# Pin_Headers.net
KiCad netlist of a schematic drawn in Altium Designer
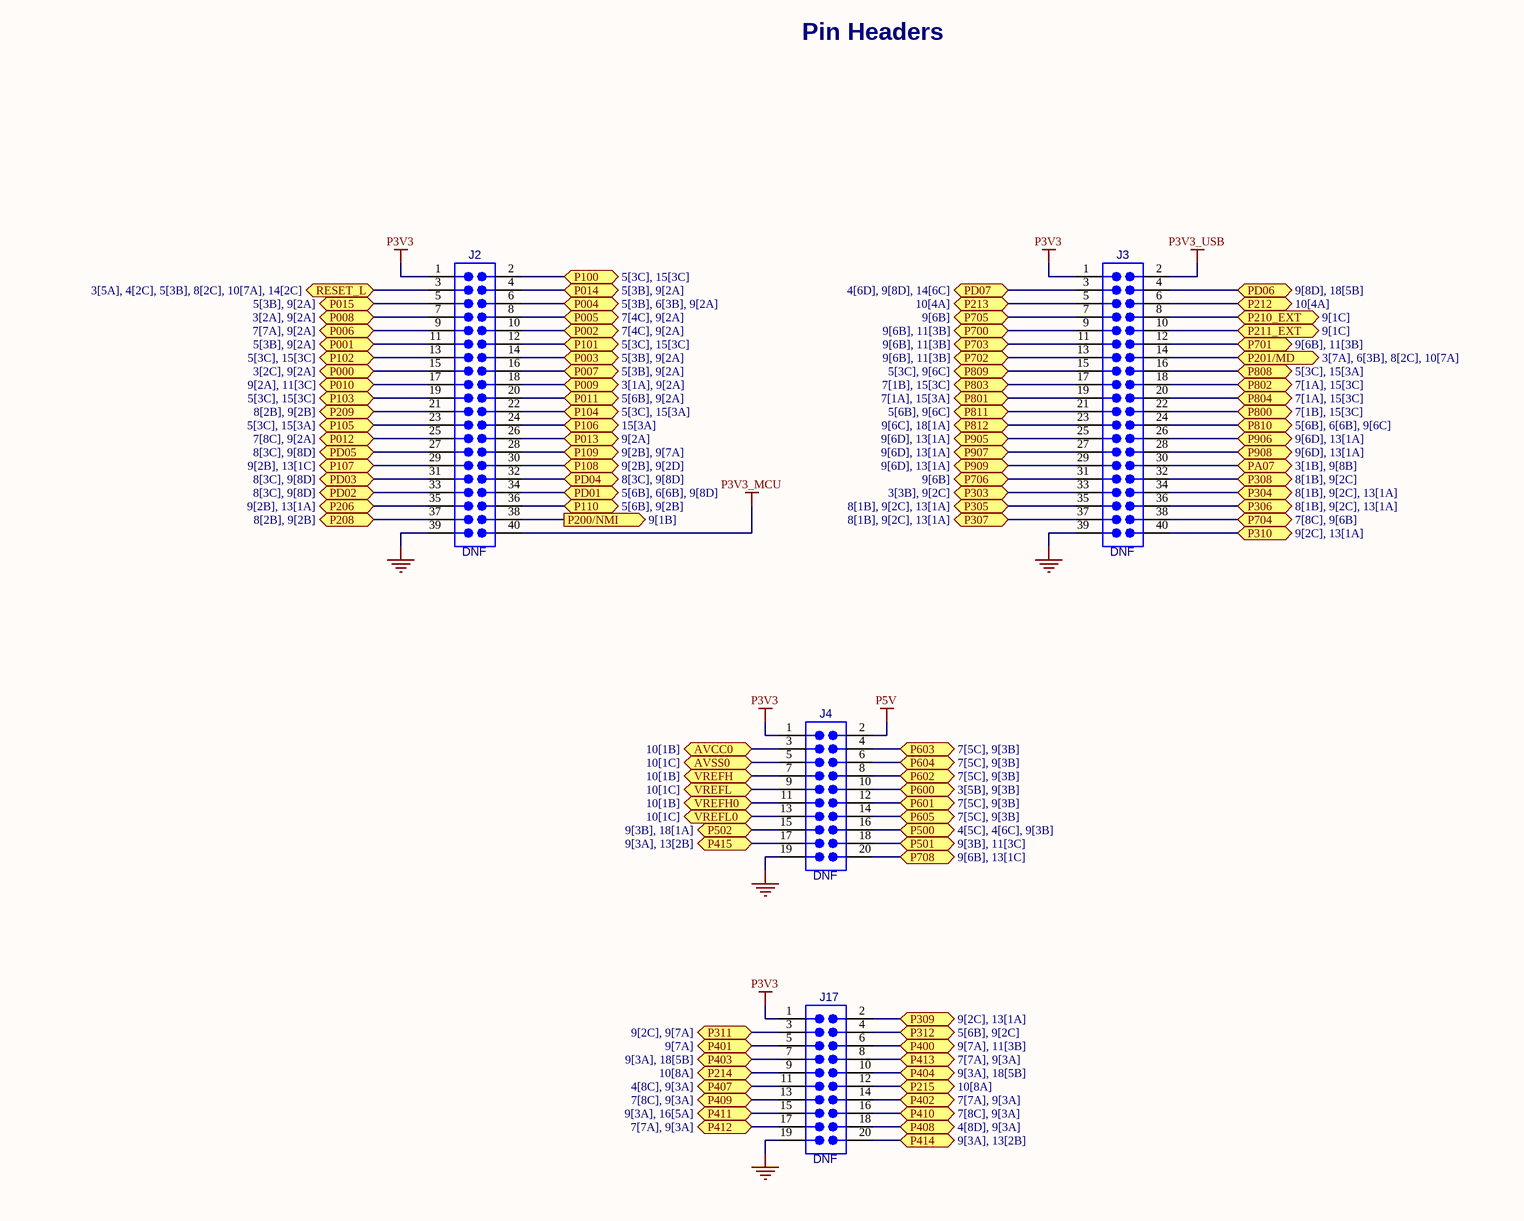
[diagram p0: Pin Headers.SchDoc]

(export (version "E")
  (design (tool "Eeschema 10.0.6"))
  (components
    (comp (ref "J2")
      (value "CON_040")
      (footprint "wue_61304021121")
      (description "Header,40way,2row,vertical,2.54mm,THT")
      (fields (field (name "DNF") "DNF"))
      (libsource (lib "ek-ra8d2_mp - Customer") (part "CON_040"))
    )
    (comp (ref "J3")
      (value "CON_040")
      (footprint "wue_61304021121")
      (description "Header,40way,2row,vertical,2.54mm,THT")
      (fields (field (name "DNF") "DNF"))
      (libsource (lib "ek-ra8d2_mp - Customer") (part "CON_040"))
    )
    (comp (ref "J4")
      (value "CON_020")
      (footprint "wue_61302021121")
      (description "Header,20way,2row,vertical,2.54mm,THT")
      (fields (field (name "DNF") "DNF"))
      (libsource (lib "ek-ra8d2_mp - Customer") (part "CON_020"))
    )
    (comp (ref "J17")
      (value "CON_020")
      (footprint "wue_61302021121")
      (description "Header,20way,2row,vertical,2.54mm,THT")
      (fields (field (name "DNF") "DNF"))
      (libsource (lib "ek-ra8d2_mp - Customer") (part "CON_020"))
    )
  )
  (nets
    (net (code "1") (name "/AVCC0") (class "Default")
      (node (ref "J4") (pin "3") (pinfunction "3_3") (pintype "passive"))
    )
    (net (code "2") (name "/AVSS0") (class "Default")
      (node (ref "J4") (pin "5") (pinfunction "5_5") (pintype "passive"))
    )
    (net (code "3") (name "/P000") (class "Default")
      (node (ref "J2") (pin "15") (pinfunction "15_15") (pintype "passive"))
    )
    (net (code "4") (name "/P001") (class "Default")
      (node (ref "J2") (pin "11") (pinfunction "11_11") (pintype "passive"))
    )
    (net (code "5") (name "/P002") (class "Default")
      (node (ref "J2") (pin "10") (pinfunction "10_10") (pintype "passive"))
    )
    (net (code "6") (name "/P003") (class "Default")
      (node (ref "J2") (pin "14") (pinfunction "14_14") (pintype "passive"))
    )
    (net (code "7") (name "/P004") (class "Default")
      (node (ref "J2") (pin "6") (pinfunction "6_6") (pintype "passive"))
    )
    (net (code "8") (name "/P005") (class "Default")
      (node (ref "J2") (pin "8") (pinfunction "8_8") (pintype "passive"))
    )
    (net (code "9") (name "/P006") (class "Default")
      (node (ref "J2") (pin "9") (pinfunction "9_9") (pintype "passive"))
    )
    (net (code "10") (name "/P007") (class "Default")
      (node (ref "J2") (pin "16") (pinfunction "16_16") (pintype "passive"))
    )
    (net (code "11") (name "/P008") (class "Default")
      (node (ref "J2") (pin "7") (pinfunction "7_7") (pintype "passive"))
    )
    (net (code "12") (name "/P009") (class "Default")
      (node (ref "J2") (pin "18") (pinfunction "18_18") (pintype "passive"))
    )
    (net (code "13") (name "/P010") (class "Default")
      (node (ref "J2") (pin "17") (pinfunction "17_17") (pintype "passive"))
    )
    (net (code "14") (name "/P011") (class "Default")
      (node (ref "J2") (pin "20") (pinfunction "20_20") (pintype "passive"))
    )
    (net (code "15") (name "/P012") (class "Default")
      (node (ref "J2") (pin "25") (pinfunction "25_25") (pintype "passive"))
    )
    (net (code "16") (name "/P013") (class "Default")
      (node (ref "J2") (pin "26") (pinfunction "26_26") (pintype "passive"))
    )
    (net (code "17") (name "/P014") (class "Default")
      (node (ref "J2") (pin "4") (pinfunction "4_4") (pintype "passive"))
    )
    (net (code "18") (name "/P015") (class "Default")
      (node (ref "J2") (pin "5") (pinfunction "5_5") (pintype "passive"))
    )
    (net (code "19") (name "/P100") (class "Default")
      (node (ref "J2") (pin "2") (pinfunction "2_2") (pintype "passive"))
    )
    (net (code "20") (name "/P101") (class "Default")
      (node (ref "J2") (pin "12") (pinfunction "12_12") (pintype "passive"))
    )
    (net (code "21") (name "/P102") (class "Default")
      (node (ref "J2") (pin "13") (pinfunction "13_13") (pintype "passive"))
    )
    (net (code "22") (name "/P103") (class "Default")
      (node (ref "J2") (pin "19") (pinfunction "19_19") (pintype "passive"))
    )
    (net (code "23") (name "/P104") (class "Default")
      (node (ref "J2") (pin "22") (pinfunction "22_22") (pintype "passive"))
    )
    (net (code "24") (name "/P105") (class "Default")
      (node (ref "J2") (pin "23") (pinfunction "23_23") (pintype "passive"))
    )
    (net (code "25") (name "/P106") (class "Default")
      (node (ref "J2") (pin "24") (pinfunction "24_24") (pintype "passive"))
    )
    (net (code "26") (name "/P107") (class "Default")
      (node (ref "J2") (pin "29") (pinfunction "29_29") (pintype "passive"))
    )
    (net (code "27") (name "/P108") (class "Default")
      (node (ref "J2") (pin "30") (pinfunction "30_30") (pintype "passive"))
    )
    (net (code "28") (name "/P109") (class "Default")
      (node (ref "J2") (pin "28") (pinfunction "28_28") (pintype "passive"))
    )
    (net (code "29") (name "/P110") (class "Default")
      (node (ref "J2") (pin "36") (pinfunction "36_36") (pintype "passive"))
    )
    (net (code "30") (name "/P200{slash}NMI") (class "Default")
      (node (ref "J2") (pin "38") (pinfunction "38_38") (pintype "passive"))
    )
    (net (code "31") (name "/P201{slash}MD") (class "Default")
      (node (ref "J3") (pin "14") (pinfunction "14_14") (pintype "passive"))
    )
    (net (code "32") (name "/P206") (class "Default")
      (node (ref "J2") (pin "35") (pinfunction "35_35") (pintype "passive"))
    )
    (net (code "33") (name "/P208") (class "Default")
      (node (ref "J2") (pin "37") (pinfunction "37_37") (pintype "passive"))
    )
    (net (code "34") (name "/P209") (class "Default")
      (node (ref "J2") (pin "21") (pinfunction "21_21") (pintype "passive"))
    )
    (net (code "35") (name "/P210_EXT") (class "Default")
      (node (ref "J3") (pin "8") (pinfunction "8_8") (pintype "passive"))
    )
    (net (code "36") (name "/P211_EXT") (class "Default")
      (node (ref "J3") (pin "10") (pinfunction "10_10") (pintype "passive"))
    )
    (net (code "37") (name "/P212") (class "Default")
      (node (ref "J3") (pin "6") (pinfunction "6_6") (pintype "passive"))
    )
    (net (code "38") (name "/P213") (class "Default")
      (node (ref "J3") (pin "5") (pinfunction "5_5") (pintype "passive"))
    )
    (net (code "39") (name "/P214") (class "Default")
      (node (ref "J17") (pin "9") (pinfunction "9_9") (pintype "passive"))
    )
    (net (code "40") (name "/P215") (class "Default")
      (node (ref "J17") (pin "12") (pinfunction "12_12") (pintype "passive"))
    )
    (net (code "41") (name "/P303") (class "Default")
      (node (ref "J3") (pin "33") (pinfunction "33_33") (pintype "passive"))
    )
    (net (code "42") (name "/P304") (class "Default")
      (node (ref "J3") (pin "34") (pinfunction "34_34") (pintype "passive"))
    )
    (net (code "43") (name "/P305") (class "Default")
      (node (ref "J3") (pin "35") (pinfunction "35_35") (pintype "passive"))
    )
    (net (code "44") (name "/P306") (class "Default")
      (node (ref "J3") (pin "36") (pinfunction "36_36") (pintype "passive"))
    )
    (net (code "45") (name "/P307") (class "Default")
      (node (ref "J3") (pin "37") (pinfunction "37_37") (pintype "passive"))
    )
    (net (code "46") (name "/P308") (class "Default")
      (node (ref "J3") (pin "32") (pinfunction "32_32") (pintype "passive"))
    )
    (net (code "47") (name "/P309") (class "Default")
      (node (ref "J17") (pin "2") (pinfunction "2_2") (pintype "passive"))
    )
    (net (code "48") (name "/P310") (class "Default")
      (node (ref "J3") (pin "40") (pinfunction "40_40") (pintype "passive"))
    )
    (net (code "49") (name "/P311") (class "Default")
      (node (ref "J17") (pin "3") (pinfunction "3_3") (pintype "passive"))
    )
    (net (code "50") (name "/P312") (class "Default")
      (node (ref "J17") (pin "4") (pinfunction "4_4") (pintype "passive"))
    )
    (net (code "51") (name "/P400") (class "Default")
      (node (ref "J17") (pin "6") (pinfunction "6_6") (pintype "passive"))
    )
    (net (code "52") (name "/P401") (class "Default")
      (node (ref "J17") (pin "5") (pinfunction "5_5") (pintype "passive"))
    )
    (net (code "53") (name "/P402") (class "Default")
      (node (ref "J17") (pin "14") (pinfunction "14_14") (pintype "passive"))
    )
    (net (code "54") (name "/P403") (class "Default")
      (node (ref "J17") (pin "7") (pinfunction "7_7") (pintype "passive"))
    )
    (net (code "55") (name "/P404") (class "Default")
      (node (ref "J17") (pin "10") (pinfunction "10_10") (pintype "passive"))
    )
    (net (code "56") (name "/P407") (class "Default")
      (node (ref "J17") (pin "11") (pinfunction "11_11") (pintype "passive"))
    )
    (net (code "57") (name "/P408") (class "Default")
      (node (ref "J17") (pin "18") (pinfunction "18_18") (pintype "passive"))
    )
    (net (code "58") (name "/P409") (class "Default")
      (node (ref "J17") (pin "13") (pinfunction "13_13") (pintype "passive"))
    )
    (net (code "59") (name "/P410") (class "Default")
      (node (ref "J17") (pin "16") (pinfunction "16_16") (pintype "passive"))
    )
    (net (code "60") (name "/P411") (class "Default")
      (node (ref "J17") (pin "15") (pinfunction "15_15") (pintype "passive"))
    )
    (net (code "61") (name "/P412") (class "Default")
      (node (ref "J17") (pin "17") (pinfunction "17_17") (pintype "passive"))
    )
    (net (code "62") (name "/P413") (class "Default")
      (node (ref "J17") (pin "8") (pinfunction "8_8") (pintype "passive"))
    )
    (net (code "63") (name "/P414") (class "Default")
      (node (ref "J17") (pin "20") (pinfunction "20_20") (pintype "passive"))
    )
    (net (code "64") (name "/P415") (class "Default")
      (node (ref "J4") (pin "17") (pinfunction "17_17") (pintype "passive"))
    )
    (net (code "65") (name "/P500") (class "Default")
      (node (ref "J4") (pin "16") (pinfunction "16_16") (pintype "passive"))
    )
    (net (code "66") (name "/P501") (class "Default")
      (node (ref "J4") (pin "18") (pinfunction "18_18") (pintype "passive"))
    )
    (net (code "67") (name "/P502") (class "Default")
      (node (ref "J4") (pin "15") (pinfunction "15_15") (pintype "passive"))
    )
    (net (code "68") (name "/P600") (class "Default")
      (node (ref "J4") (pin "10") (pinfunction "10_10") (pintype "passive"))
    )
    (net (code "69") (name "/P601") (class "Default")
      (node (ref "J4") (pin "12") (pinfunction "12_12") (pintype "passive"))
    )
    (net (code "70") (name "/P602") (class "Default")
      (node (ref "J4") (pin "8") (pinfunction "8_8") (pintype "passive"))
    )
    (net (code "71") (name "/P603") (class "Default")
      (node (ref "J4") (pin "4") (pinfunction "4_4") (pintype "passive"))
    )
    (net (code "72") (name "/P604") (class "Default")
      (node (ref "J4") (pin "6") (pinfunction "6_6") (pintype "passive"))
    )
    (net (code "73") (name "/P605") (class "Default")
      (node (ref "J4") (pin "14") (pinfunction "14_14") (pintype "passive"))
    )
    (net (code "74") (name "/P700") (class "Default")
      (node (ref "J3") (pin "9") (pinfunction "9_9") (pintype "passive"))
    )
    (net (code "75") (name "/P701") (class "Default")
      (node (ref "J3") (pin "12") (pinfunction "12_12") (pintype "passive"))
    )
    (net (code "76") (name "/P702") (class "Default")
      (node (ref "J3") (pin "13") (pinfunction "13_13") (pintype "passive"))
    )
    (net (code "77") (name "/P703") (class "Default")
      (node (ref "J3") (pin "11") (pinfunction "11_11") (pintype "passive"))
    )
    (net (code "78") (name "/P704") (class "Default")
      (node (ref "J3") (pin "38") (pinfunction "38_38") (pintype "passive"))
    )
    (net (code "79") (name "/P705") (class "Default")
      (node (ref "J3") (pin "7") (pinfunction "7_7") (pintype "passive"))
    )
    (net (code "80") (name "/P706") (class "Default")
      (node (ref "J3") (pin "31") (pinfunction "31_31") (pintype "passive"))
    )
    (net (code "81") (name "/P708") (class "Default")
      (node (ref "J4") (pin "20") (pinfunction "20_20") (pintype "passive"))
    )
    (net (code "82") (name "/P800") (class "Default")
      (node (ref "J3") (pin "22") (pinfunction "22_22") (pintype "passive"))
    )
    (net (code "83") (name "/P801") (class "Default")
      (node (ref "J3") (pin "19") (pinfunction "19_19") (pintype "passive"))
    )
    (net (code "84") (name "/P802") (class "Default")
      (node (ref "J3") (pin "18") (pinfunction "18_18") (pintype "passive"))
    )
    (net (code "85") (name "/P803") (class "Default")
      (node (ref "J3") (pin "17") (pinfunction "17_17") (pintype "passive"))
    )
    (net (code "86") (name "/P804") (class "Default")
      (node (ref "J3") (pin "20") (pinfunction "20_20") (pintype "passive"))
    )
    (net (code "87") (name "/P808") (class "Default")
      (node (ref "J3") (pin "16") (pinfunction "16_16") (pintype "passive"))
    )
    (net (code "88") (name "/P809") (class "Default")
      (node (ref "J3") (pin "15") (pinfunction "15_15") (pintype "passive"))
    )
    (net (code "89") (name "/P810") (class "Default")
      (node (ref "J3") (pin "24") (pinfunction "24_24") (pintype "passive"))
    )
    (net (code "90") (name "/P811") (class "Default")
      (node (ref "J3") (pin "21") (pinfunction "21_21") (pintype "passive"))
    )
    (net (code "91") (name "/P812") (class "Default")
      (node (ref "J3") (pin "23") (pinfunction "23_23") (pintype "passive"))
    )
    (net (code "92") (name "/P905") (class "Default")
      (node (ref "J3") (pin "25") (pinfunction "25_25") (pintype "passive"))
    )
    (net (code "93") (name "/P906") (class "Default")
      (node (ref "J3") (pin "26") (pinfunction "26_26") (pintype "passive"))
    )
    (net (code "94") (name "/P907") (class "Default")
      (node (ref "J3") (pin "27") (pinfunction "27_27") (pintype "passive"))
    )
    (net (code "95") (name "/P908") (class "Default")
      (node (ref "J3") (pin "28") (pinfunction "28_28") (pintype "passive"))
    )
    (net (code "96") (name "/P909") (class "Default")
      (node (ref "J3") (pin "29") (pinfunction "29_29") (pintype "passive"))
    )
    (net (code "97") (name "/PA07") (class "Default")
      (node (ref "J3") (pin "30") (pinfunction "30_30") (pintype "passive"))
    )
    (net (code "98") (name "/PD01") (class "Default")
      (node (ref "J2") (pin "34") (pinfunction "34_34") (pintype "passive"))
    )
    (net (code "99") (name "/PD02") (class "Default")
      (node (ref "J2") (pin "33") (pinfunction "33_33") (pintype "passive"))
    )
    (net (code "100") (name "/PD03") (class "Default")
      (node (ref "J2") (pin "31") (pinfunction "31_31") (pintype "passive"))
    )
    (net (code "101") (name "/PD04") (class "Default")
      (node (ref "J2") (pin "32") (pinfunction "32_32") (pintype "passive"))
    )
    (net (code "102") (name "/PD05") (class "Default")
      (node (ref "J2") (pin "27") (pinfunction "27_27") (pintype "passive"))
    )
    (net (code "103") (name "/PD06") (class "Default")
      (node (ref "J3") (pin "4") (pinfunction "4_4") (pintype "passive"))
    )
    (net (code "104") (name "/PD07") (class "Default")
      (node (ref "J3") (pin "3") (pinfunction "3_3") (pintype "passive"))
    )
    (net (code "105") (name "/RESET_L") (class "Default")
      (node (ref "J2") (pin "3") (pinfunction "3_3") (pintype "passive"))
    )
    (net (code "106") (name "/VREFH") (class "Default")
      (node (ref "J4") (pin "7") (pinfunction "7_7") (pintype "passive"))
    )
    (net (code "107") (name "/VREFH0") (class "Default")
      (node (ref "J4") (pin "11") (pinfunction "11_11") (pintype "passive"))
    )
    (net (code "108") (name "/VREFL") (class "Default")
      (node (ref "J4") (pin "9") (pinfunction "9_9") (pintype "passive"))
    )
    (net (code "109") (name "/VREFL0") (class "Default")
      (node (ref "J4") (pin "13") (pinfunction "13_13") (pintype "passive"))
    )
    (net (code "110") (name "GND") (class "Default")
      (node (ref "J17") (pin "19") (pinfunction "19_19") (pintype "passive"))
      (node (ref "J2") (pin "39") (pinfunction "39_39") (pintype "passive"))
      (node (ref "J3") (pin "39") (pinfunction "39_39") (pintype "passive"))
      (node (ref "J4") (pin "19") (pinfunction "19_19") (pintype "passive"))
    )
    (net (code "111") (name "P3V3") (class "Default")
      (node (ref "J17") (pin "1") (pinfunction "1_1") (pintype "passive"))
      (node (ref "J2") (pin "1") (pinfunction "1_1") (pintype "passive"))
      (node (ref "J3") (pin "1") (pinfunction "1_1") (pintype "passive"))
      (node (ref "J4") (pin "1") (pinfunction "1_1") (pintype "passive"))
    )
    (net (code "112") (name "P3V3_MCU") (class "Default")
      (node (ref "J2") (pin "40") (pinfunction "40_40") (pintype "passive"))
    )
    (net (code "113") (name "P3V3_USB") (class "Default")
      (node (ref "J3") (pin "2") (pinfunction "2_2") (pintype "passive"))
    )
    (net (code "114") (name "P5V") (class "Default")
      (node (ref "J4") (pin "2") (pinfunction "2_2") (pintype "passive"))
    )
  )
)
